# DimmerSaldatore.net
KiCad netlist of a schematic drawn in EAGLE
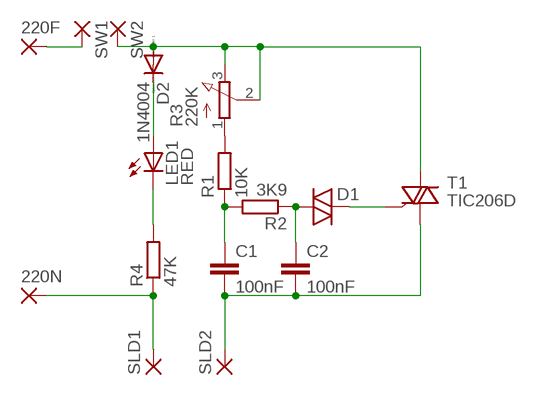
[diagram p0: schematic, sheet 1]

(export (version "E")
  (design (tool "Eeschema 10.0.6"))
  (components
    (comp (ref "220F")
      (value "3,81/1,4")
      (footprint "eagle-import:3,81_1,4")
      (libsource (lib "eagle-import") (part "3,81/1,4"))
    )
    (comp (ref "220N")
      (value "3,81/1,4")
      (footprint "eagle-import:3,81_1,4")
      (libsource (lib "eagle-import") (part "3,81/1,4"))
    )
    (comp (ref "C1")
      (value "100nF")
      (footprint "eagle-import:C075-052X106")
      (libsource (lib "eagle-import") (part "C-EU075-052X106"))
    )
    (comp (ref "C2")
      (value "100nF")
      (footprint "eagle-import:C075-052X106")
      (libsource (lib "eagle-import") (part "C-EU075-052X106"))
    )
    (comp (ref "D1")
      (value "DIAC-GT32")
      (footprint "eagle-import:GT32")
      (libsource (lib "eagle-import") (part "DIAC-GT32"))
    )
    (comp (ref "D2")
      (value "1N4004")
      (footprint "eagle-import:DO41-10")
      (libsource (lib "eagle-import") (part "1N4004"))
    )
    (comp (ref "LED1")
      (value "RED")
      (footprint "eagle-import:LED5MM")
      (libsource (lib "eagle-import") (part "LED5MM"))
    )
    (comp (ref "R1")
      (value "10K")
      (footprint "eagle-import:0204_7")
      (libsource (lib "eagle-import") (part "R-EU_0204/7"))
    )
    (comp (ref "R2")
      (value "3K9")
      (footprint "eagle-import:0204_7")
      (libsource (lib "eagle-import") (part "R-EU_0204/7"))
    )
    (comp (ref "R3")
      (value "220K")
      (footprint "eagle-import:3RP_1610N")
      (libsource (lib "eagle-import") (part "3RP/1610N"))
    )
    (comp (ref "R4")
      (value "47K")
      (footprint "eagle-import:0204_7")
      (libsource (lib "eagle-import") (part "R-EU_0204/7"))
    )
    (comp (ref "SLD1")
      (value "3,81/1,4")
      (footprint "eagle-import:3,81_1,4")
      (libsource (lib "eagle-import") (part "3,81/1,4"))
    )
    (comp (ref "SLD2")
      (value "3,81/1,4")
      (footprint "eagle-import:3,81_1,4")
      (libsource (lib "eagle-import") (part "3,81/1,4"))
    )
    (comp (ref "SW1")
      (value "3,81/1,4")
      (footprint "eagle-import:3,81_1,4")
      (libsource (lib "eagle-import") (part "3,81/1,4"))
    )
    (comp (ref "SW2")
      (value "3,81/1,4")
      (footprint "eagle-import:3,81_1,4")
      (libsource (lib "eagle-import") (part "3,81/1,4"))
    )
    (comp (ref "T1")
      (value "TIC206D")
      (footprint "eagle-import:TO220BV")
      (libsource (lib "eagle-import") (part "TIC206D"))
    )
  )
  (nets
    (net (code "1") (name "Net-(220F-P)") (class "Default")
      (node (ref "220F") (pin "1") (pinfunction "P_1") (pintype "passive"))
      (node (ref "SW1") (pin "1") (pinfunction "P_1") (pintype "passive"))
    )
    (net (code "2") (name "Net-(220N-P)") (class "Default")
      (node (ref "220N") (pin "1") (pinfunction "P_1") (pintype "passive"))
      (node (ref "R4") (pin "1") (pinfunction "1_1") (pintype "passive"))
      (node (ref "SLD1") (pin "1") (pinfunction "P_1") (pintype "passive"))
    )
    (net (code "3") (name "Net-(C1-Pad1)") (class "Default")
      (node (ref "C1") (pin "1") (pinfunction "1_1") (pintype "passive"))
      (node (ref "R1") (pin "1") (pinfunction "1_1") (pintype "passive"))
      (node (ref "R2") (pin "2") (pinfunction "2_2") (pintype "passive"))
    )
    (net (code "4") (name "Net-(C2-Pad1)") (class "Default")
      (node (ref "C2") (pin "1") (pinfunction "1_1") (pintype "passive"))
      (node (ref "D1") (pin "1") (pinfunction "1_1") (pintype "passive"))
      (node (ref "R2") (pin "1") (pinfunction "1_1") (pintype "passive"))
    )
    (net (code "5") (name "Net-(D1-Pad2)") (class "Default")
      (node (ref "D1") (pin "2") (pinfunction "2_2") (pintype "passive"))
      (node (ref "T1") (pin "G") (pinfunction "G_G") (pintype "passive"))
    )
    (net (code "6") (name "Net-(D2-PadC)") (class "Default")
      (node (ref "D2") (pin "C") (pinfunction "C_C") (pintype "passive"))
      (node (ref "LED1") (pin "A") (pinfunction "A_A") (pintype "passive"))
    )
    (net (code "7") (name "Net-(LED1-C)") (class "Default")
      (node (ref "LED1") (pin "K") (pinfunction "C_K") (pintype "passive"))
      (node (ref "R4") (pin "2") (pinfunction "2_2") (pintype "passive"))
    )
    (net (code "8") (name "Net-(R3-A)") (class "Default")
      (node (ref "R1") (pin "2") (pinfunction "2_2") (pintype "passive"))
      (node (ref "R3") (pin "1") (pinfunction "A_1") (pintype "passive"))
    )
    (net (code "9") (name "Net-(R3-E)") (class "Default")
      (node (ref "D2") (pin "A") (pinfunction "A_A") (pintype "passive"))
      (node (ref "R3") (pin "2") (pinfunction "S_2") (pintype "passive"))
      (node (ref "R3") (pin "3") (pinfunction "E_3") (pintype "passive"))
      (node (ref "SW2") (pin "1") (pinfunction "P_1") (pintype "passive"))
      (node (ref "T1") (pin "T2") (pinfunction "A2_T2") (pintype "passive"))
    )
    (net (code "10") (name "Net-(SLD2-P)") (class "Default")
      (node (ref "C1") (pin "2") (pinfunction "2_2") (pintype "passive"))
      (node (ref "C2") (pin "2") (pinfunction "2_2") (pintype "passive"))
      (node (ref "SLD2") (pin "1") (pinfunction "P_1") (pintype "passive"))
      (node (ref "T1") (pin "T1") (pinfunction "A1_T1") (pintype "passive"))
    )
  )
)
